# PULSE-CONVERTER.net
KiCad netlist of a schematic drawn in EasyEDA
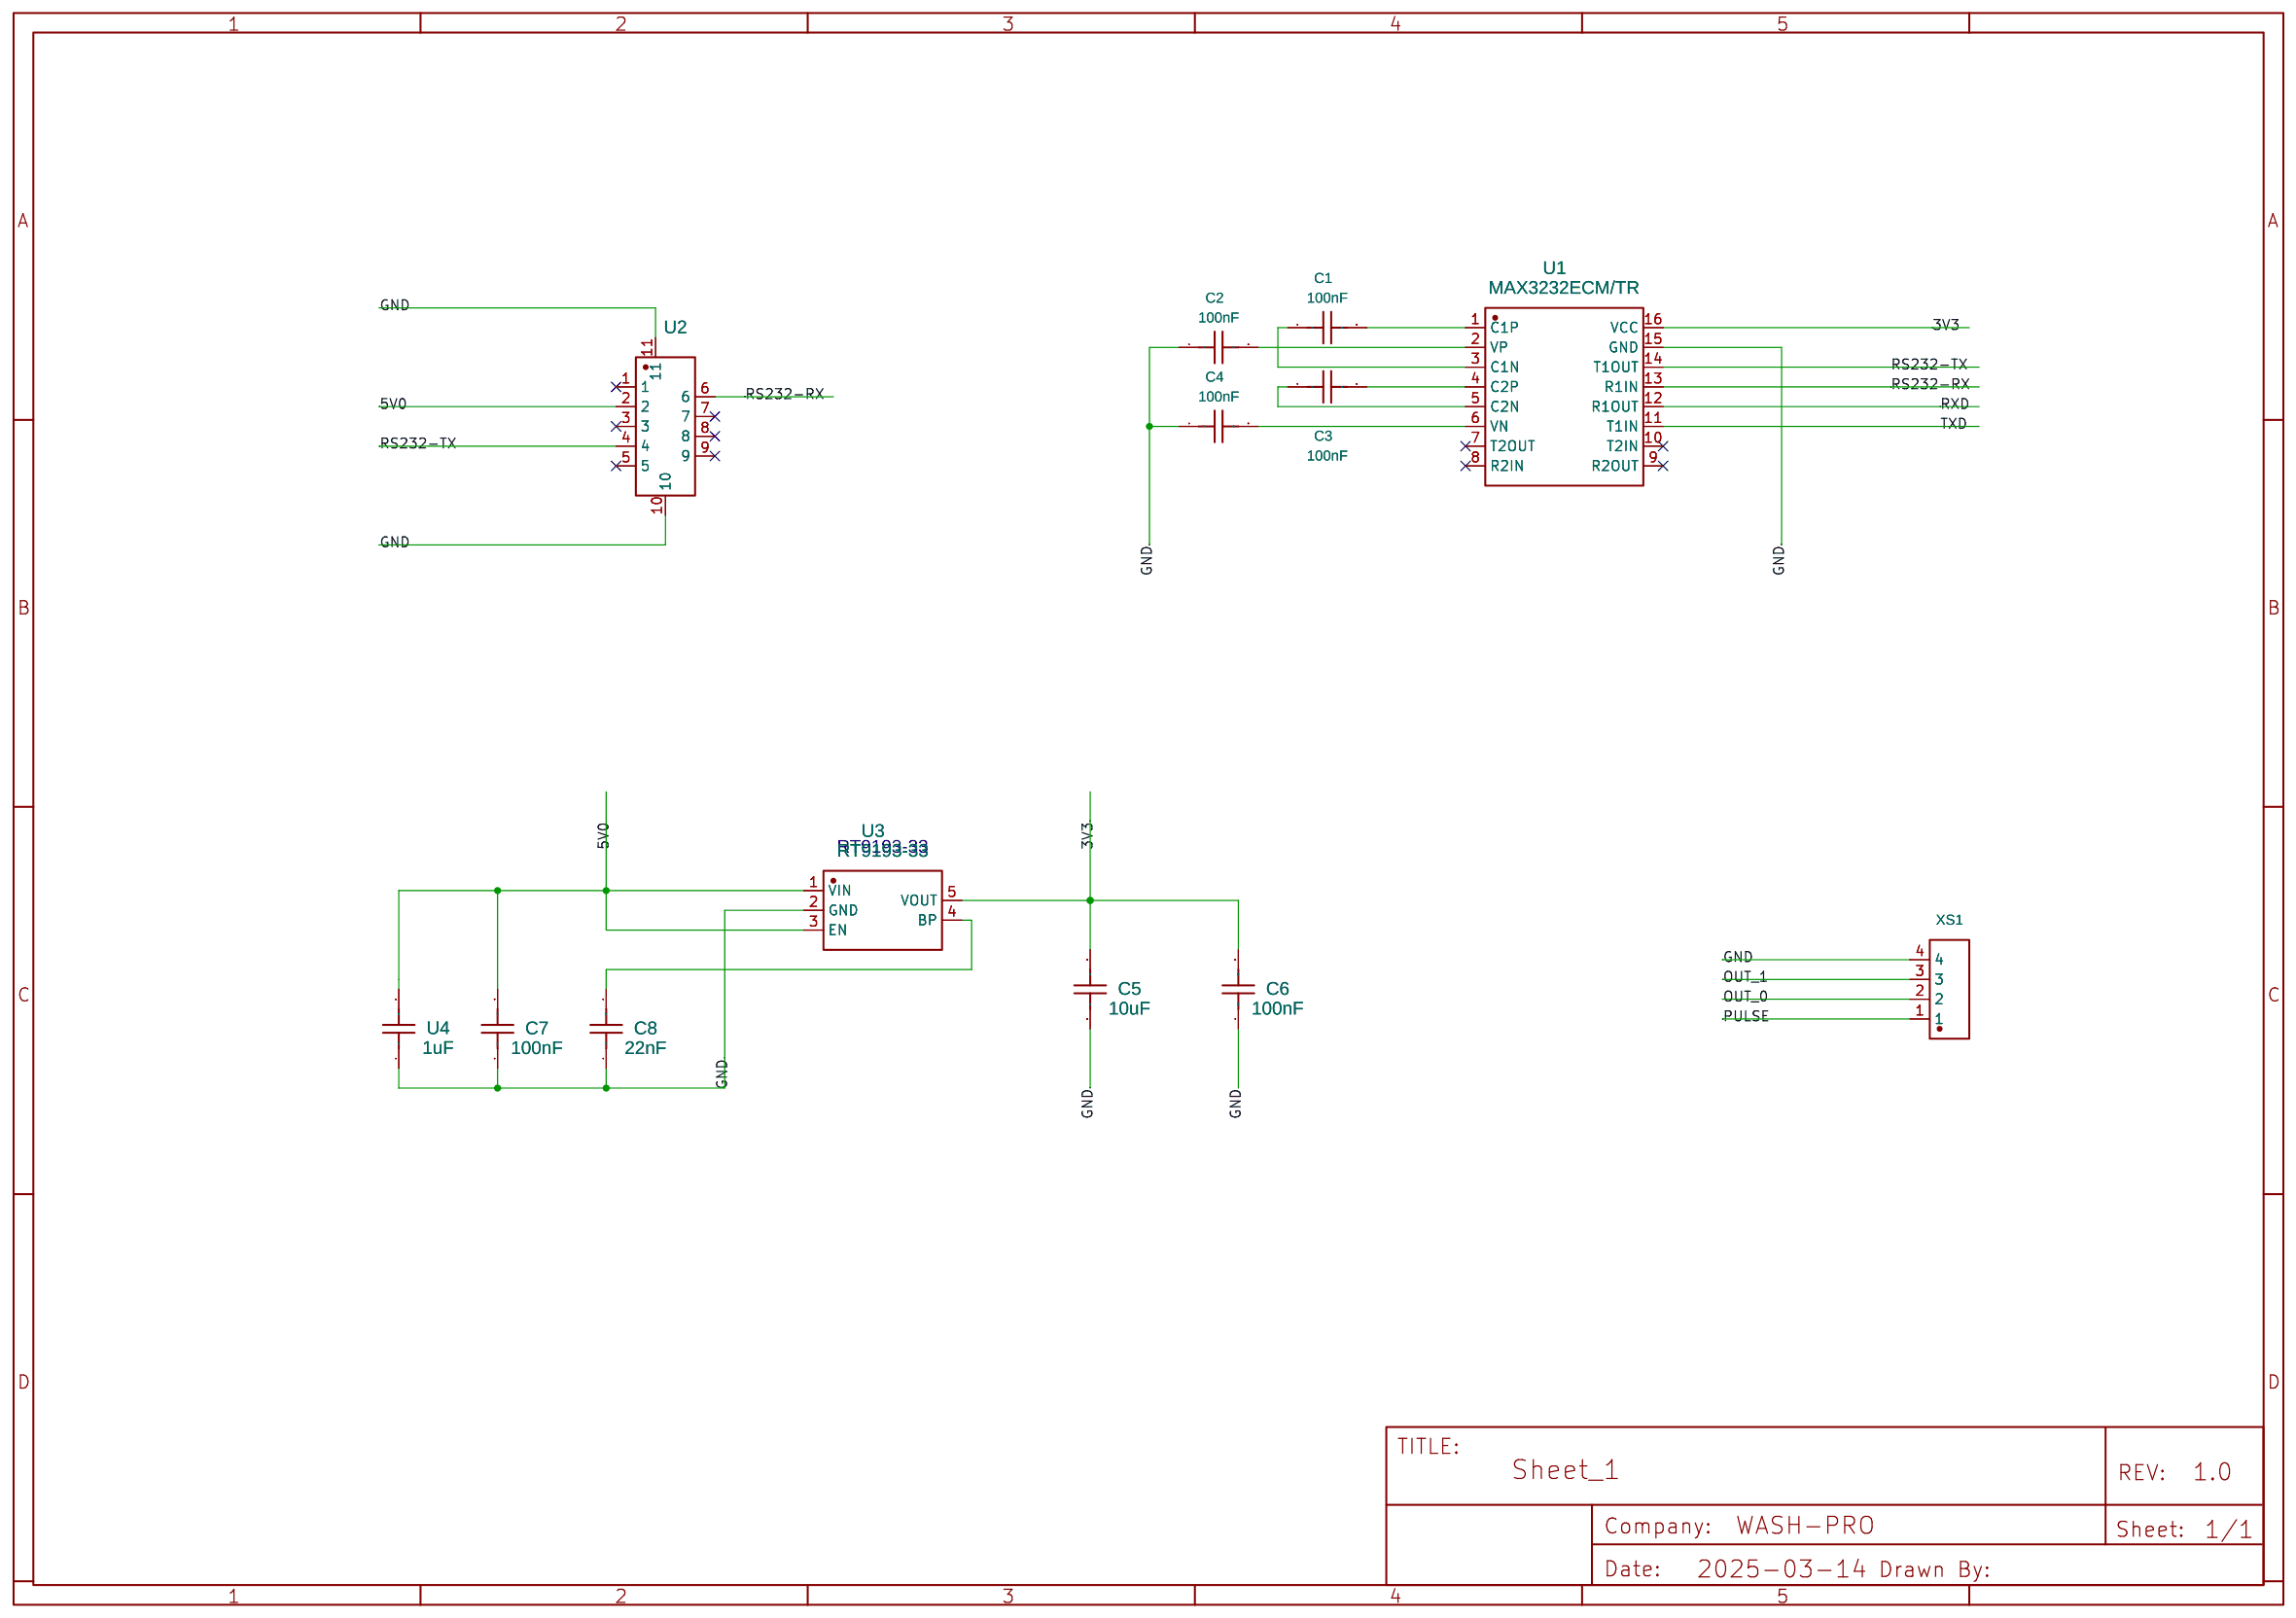
[diagram p0: Sheet_1]
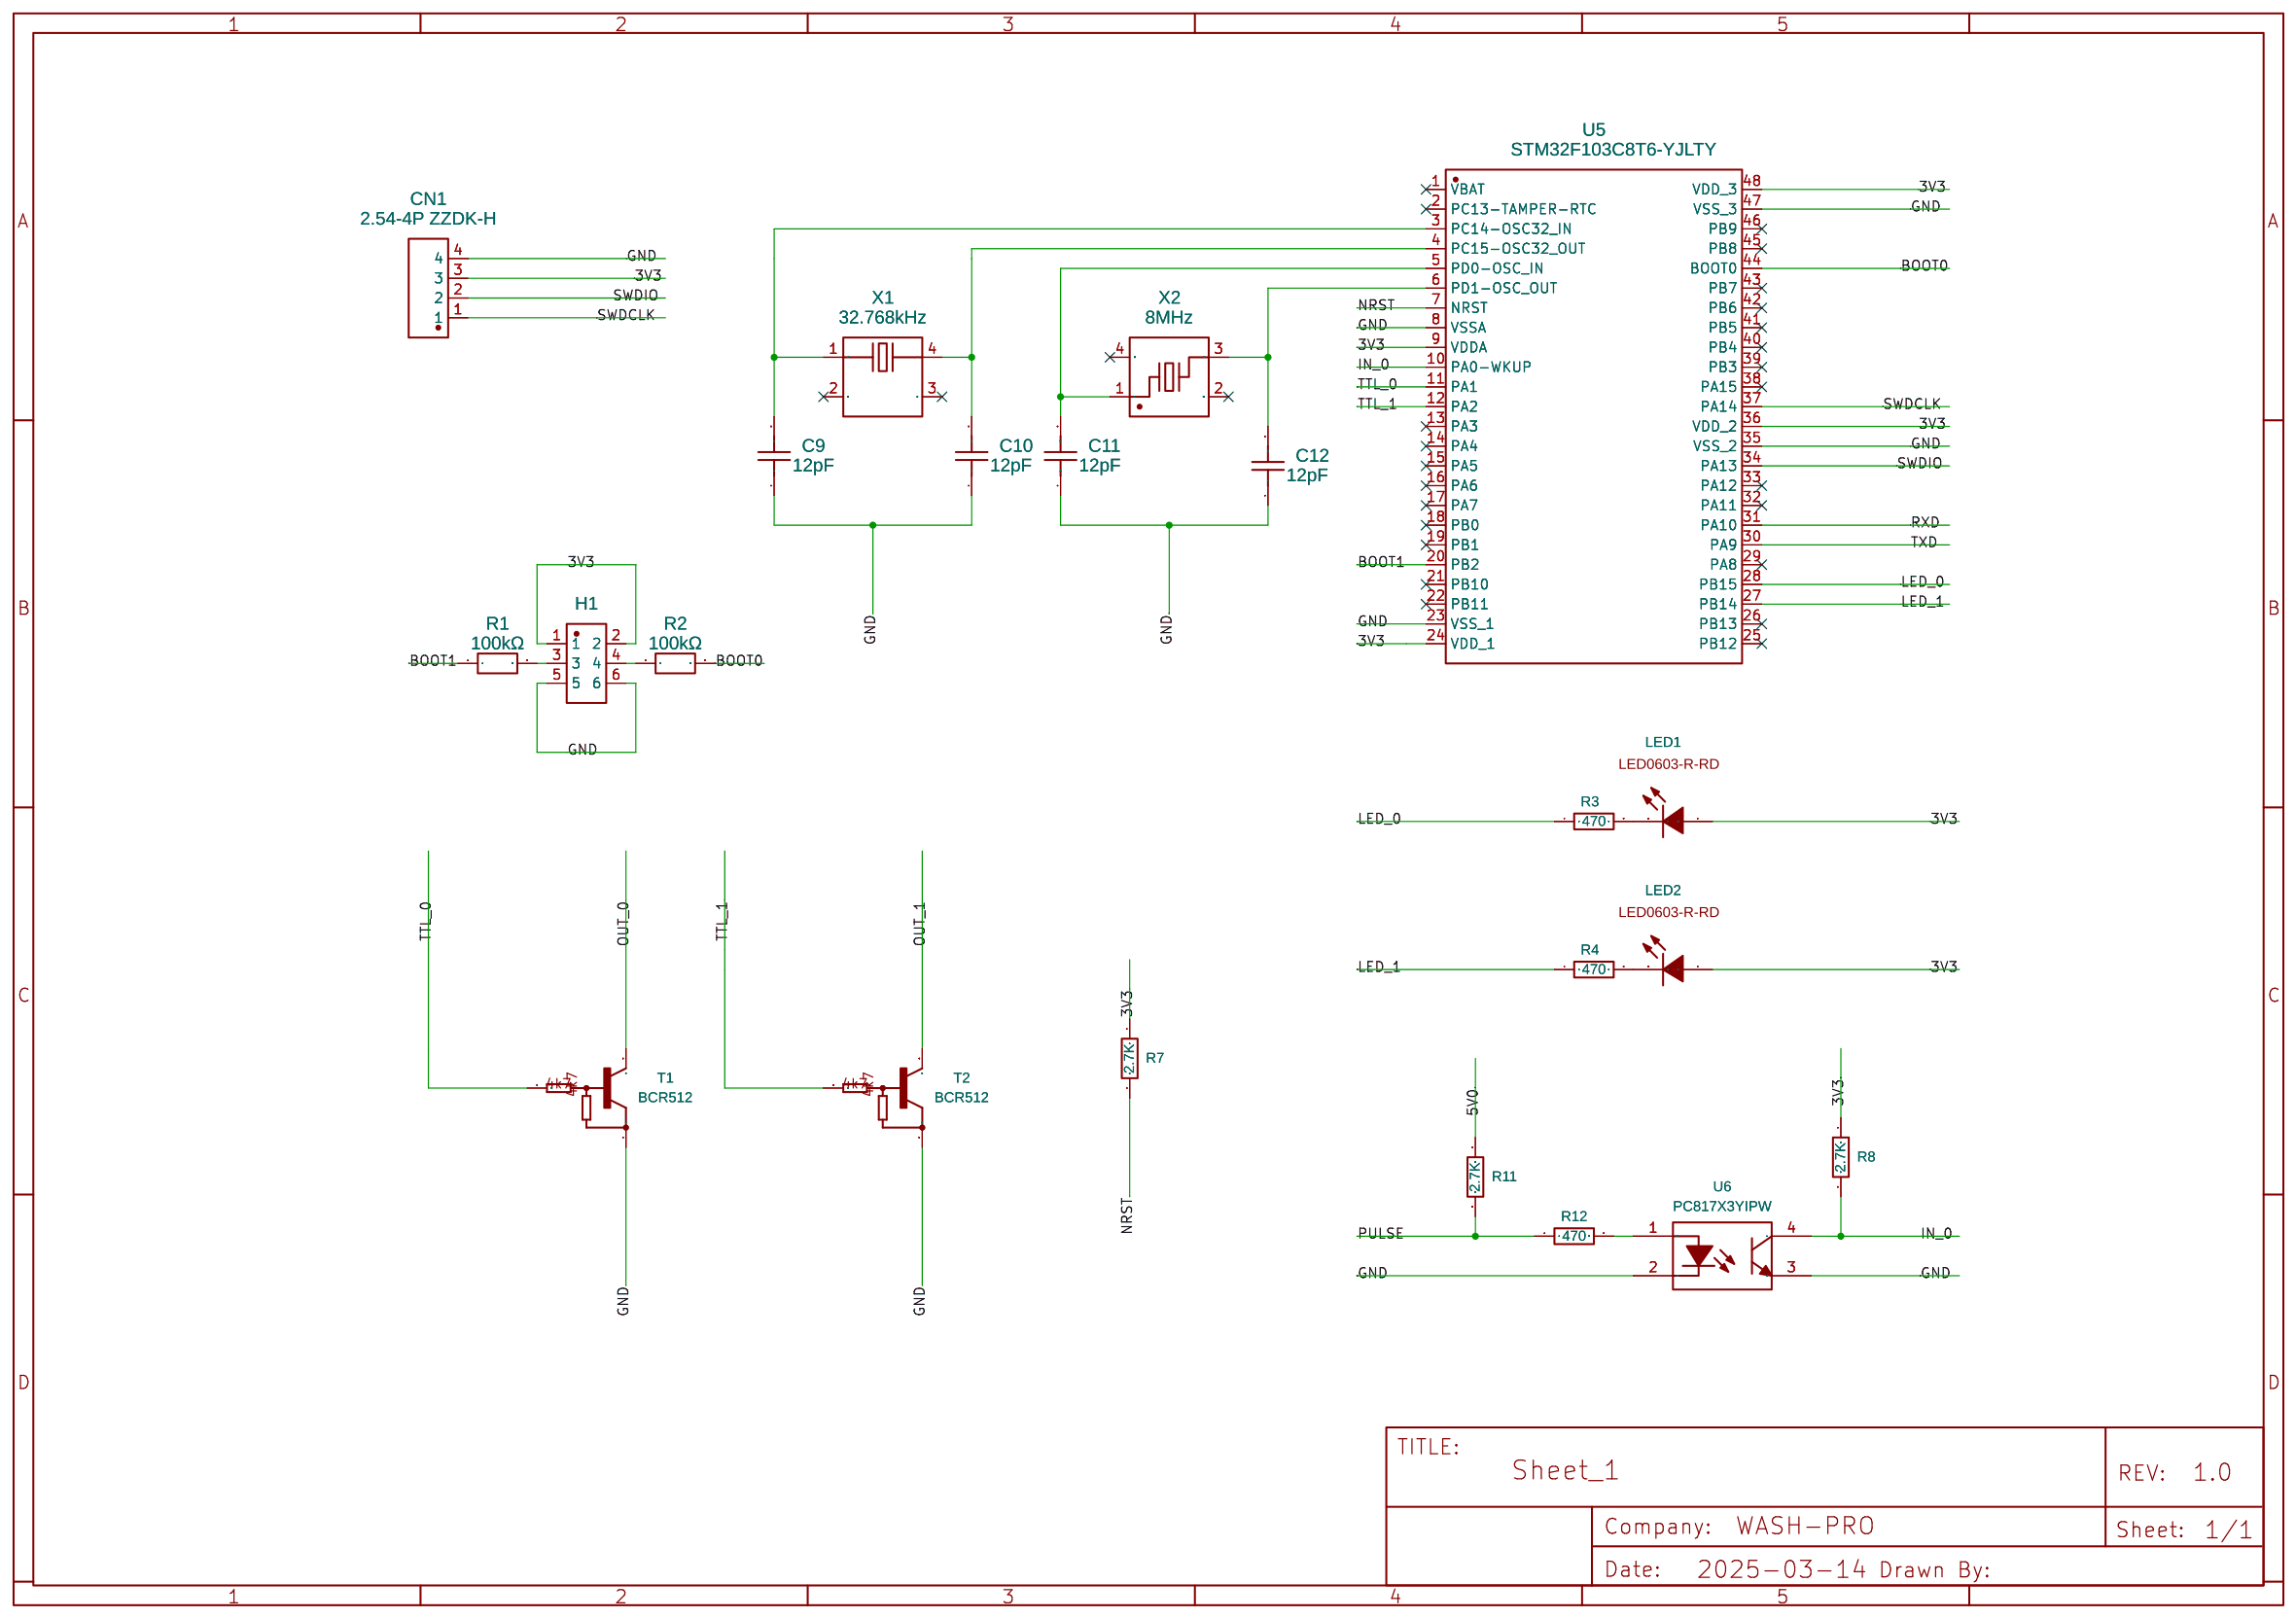
[diagram p1: Sheet_2]

(export (version "E")
  (design (tool "Eeschema 10.0.6"))
  (components
    (comp (ref "C1")
      (value "100nF")
      (fields
        (field (name "Manufacturer Part") "CL21B104KACNFNC")
        (field (name "Manufacturer") "SAMSUNG(三星)")
      )
      (libsource (lib "") (part "CL21B104KACNFNC"))
    )
    (comp (ref "C2")
      (value "100nF")
      (fields
        (field (name "Manufacturer Part") "CL21B104KACNFNC")
        (field (name "Manufacturer") "SAMSUNG(三星)")
      )
      (libsource (lib "") (part "CL21B104KACNFNC"))
    )
    (comp (ref "C3")
      (value "100nF")
      (fields
        (field (name "Manufacturer Part") "CL21B104KACNFNC")
        (field (name "Manufacturer") "SAMSUNG(三星)")
      )
      (libsource (lib "") (part "CL21B104KACNFNC"))
    )
    (comp (ref "C4")
      (value "100nF")
      (fields
        (field (name "Manufacturer Part") "CL21B104KACNFNC")
        (field (name "Manufacturer") "SAMSUNG(三星)")
      )
      (libsource (lib "") (part "CL21B104KACNFNC"))
    )
    (comp (ref "C5")
      (value "10uF")
      (fields (field (name "Manufacturer Part") "CGA4J1X7R0J106M125AD") (field (name "Manufacturer") "TDK"))
      (libsource (lib "") (part "CGA4J1X7R0J106M125AD"))
    )
    (comp (ref "C6")
      (value "100nF")
      (fields (field (name "Manufacturer Part") "C1608X5R1H104K080AA") (field (name "Manufacturer") "TDK"))
      (libsource (lib "") (part "C1608X5R1H104K080AA"))
    )
    (comp (ref "C7")
      (value "100nF")
      (fields (field (name "Manufacturer Part") "C1608X5R1H104K080AA") (field (name "Manufacturer") "TDK"))
      (libsource (lib "") (part "C1608X5R1H104K080AA"))
    )
    (comp (ref "C8")
      (value "22nF")
      (fields (field (name "Manufacturer Part") "C1608X7R2A223K080AE") (field (name "Manufacturer") "TDK"))
      (libsource (lib "") (part "C1608X7R2A223K080AE_C3843204"))
    )
    (comp (ref "U1")
      (value "MAX3232ECM/TR")
      (fields (field (name "Manufacturer") "HGSEMI(华冠)"))
      (libsource (lib "") (part "MAX3232ECM/TR"))
    )
    (comp (ref "U2")
      (value "618009211821")
      (fields (field (name "Manufacturer") "Wurth(伍尔特)"))
      (libsource (lib "") (part "618009211821"))
    )
    (comp (ref "U3") (value "RT9193-33") (libsource (lib "") (part "RT9193-33")))
    (comp (ref "U4")
      (value "1uF")
      (fields (field (name "Manufacturer Part") "C2012X5R1C105M085AA") (field (name "Manufacturer") "TDK"))
      (libsource (lib "") (part "C2012X5R1C105M085AA"))
    )
    (comp (ref "XS1")
      (value "XY2500V-E-3.81-4P")
      (fields (field (name "Manufacturer") "XINLAIYA(新莱亚)"))
      (libsource (lib "") (part "XY2500V-E-3.81-4P"))
    )
    (comp (ref "C9")
      (value "12pF")
      (fields (field (name "Manufacturer Part") "C1608NP01H120J080AA") (field (name "Manufacturer") "TDK"))
      (libsource (lib "") (part "C1608NP01H120J080AA"))
    )
    (comp (ref "C10")
      (value "12pF")
      (fields (field (name "Manufacturer Part") "C1608NP01H120J080AA") (field (name "Manufacturer") "TDK"))
      (libsource (lib "") (part "C1608NP01H120J080AA"))
    )
    (comp (ref "C11")
      (value "12pF")
      (fields (field (name "Manufacturer Part") "C1608NP01H120J080AA") (field (name "Manufacturer") "TDK"))
      (libsource (lib "") (part "C1608NP01H120J080AA"))
    )
    (comp (ref "C12")
      (value "12pF")
      (fields (field (name "Manufacturer Part") "C1608NP01H120J080AA") (field (name "Manufacturer") "TDK"))
      (libsource (lib "") (part "C1608NP01H120J080AA"))
    )
    (comp (ref "CN1")
      (value "2.54-4P ZZDK-H")
      (fields (field (name "Manufacturer") "SHOU HAN(首韩)"))
      (libsource (lib "") (part "2.54-4P ZZDK-H"))
    )
    (comp (ref "H1")
      (value "2.54-2*3")
      (fields (field (name "Manufacturer") "ZHOURI(洲日)"))
      (libsource (lib "") (part "2.54-2*3"))
    )
    (comp (ref "LED1")
      (value "19-217/BHC-XL2M2TY/3T")
      (fields (field (name "Manufacturer") "Everlight Elec"))
      (libsource (lib "") (part "19-217/BHC-XL2M2TY/3T"))
    )
    (comp (ref "LED2")
      (value "19-217/BHC-XL2M2TY/3T")
      (fields (field (name "Manufacturer") "Everlight Elec"))
      (libsource (lib "") (part "19-217/BHC-XL2M2TY/3T"))
    )
    (comp (ref "R1")
      (value "100kΩ")
      (fields (field (name "Manufacturer Part") "RHS-03K1003FT") (field (name "Manufacturer") "FH(风华)"))
      (libsource (lib "") (part "RHS-03K1003FT"))
    )
    (comp (ref "R2")
      (value "100kΩ")
      (fields (field (name "Manufacturer Part") "RHS-03K1003FT") (field (name "Manufacturer") "FH(风华)"))
      (libsource (lib "") (part "RHS-03K1003FT"))
    )
    (comp (ref "R3")
      (value "470")
      (fields (field (name "Manufacturer Part") "RC0603JR-07470RL") (field (name "Manufacturer") "YAGEO"))
      (libsource (lib "") (part "RC0603JR-07470RL"))
    )
    (comp (ref "R4")
      (value "470")
      (fields (field (name "Manufacturer Part") "RC0603JR-07470RL") (field (name "Manufacturer") "YAGEO"))
      (libsource (lib "") (part "RC0603JR-07470RL"))
    )
    (comp (ref "R7")
      (value "2.7K")
      (fields (field (name "Manufacturer Part") "MCR03ERTF1241") (field (name "Manufacturer") "ROHM Semicon"))
      (libsource (lib "") (part "MCR03ERTF1241"))
    )
    (comp (ref "R8")
      (value "2.7K")
      (fields (field (name "Manufacturer Part") "MCR03ERTF1241") (field (name "Manufacturer") "ROHM Semicon"))
      (libsource (lib "") (part "MCR03ERTF1241"))
    )
    (comp (ref "R11")
      (value "2.7K")
      (fields (field (name "Manufacturer Part") "MCR03ERTF1241") (field (name "Manufacturer") "ROHM Semicon"))
      (libsource (lib "") (part "MCR03ERTF1241"))
    )
    (comp (ref "R12")
      (value "470")
      (fields (field (name "Manufacturer Part") "RC0603JR-07470RL") (field (name "Manufacturer") "YAGEO"))
      (libsource (lib "") (part "RC0603JR-07470RL"))
    )
    (comp (ref "T1") (value "BCR512") (libsource (lib "") (part "BCR512")))
    (comp (ref "T2") (value "BCR512") (libsource (lib "") (part "BCR512")))
    (comp (ref "U5") (value "STM32F103C8T6-YJLTY") (libsource (lib "") (part "STM32F103C8T6-YJLTY")))
    (comp (ref "U6")
      (value "PC817X3YIPW")
      (fields (field (name "Manufacturer") "SHARP(夏普)"))
      (libsource (lib "") (part "PC817X3YIPW"))
    )
    (comp (ref "X1")
      (value "32.768kHz")
      (fields
        (field (name "Manufacturer Part") "XKZEL89CII-112YLC-32.768K")
        (field (name "Manufacturer") "YXC(扬兴晶振)")
      )
      (libsource (lib "") (part "XKZEL89CII-112YLC-32.768K"))
    )
    (comp (ref "X2")
      (value "8MHz")
      (fields (field (name "Manufacturer Part") "7U08000E10UCG") (field (name "Manufacturer") "SJK(晶科鑫)"))
      (libsource (lib "") (part "7U08000E10UCG"))
    )
  )
  (nets
    (net (code "1") (name "3V3") (class "Default")
      (node (ref "C5") (pin "2") (pinfunction "2_2") (pintype "unspecified"))
      (node (ref "C6") (pin "2") (pinfunction "2_2") (pintype "unspecified"))
      (node (ref "CN1") (pin "3") (pinfunction "3_3") (pintype "unspecified"))
      (node (ref "H1") (pin "1") (pinfunction "1_1") (pintype "unspecified"))
      (node (ref "H1") (pin "2") (pinfunction "2_2") (pintype "unspecified"))
      (node (ref "LED1") (pin "1") (pinfunction "A_1") (pintype "unspecified"))
      (node (ref "LED2") (pin "1") (pinfunction "A_1") (pintype "unspecified"))
      (node (ref "R7") (pin "1") (pinfunction "1_1") (pintype "unspecified"))
      (node (ref "R8") (pin "1") (pinfunction "1_1") (pintype "unspecified"))
      (node (ref "U1") (pin "16") (pinfunction "VCC_16") (pintype "unspecified"))
      (node (ref "U3") (pin "5") (pinfunction "VOUT_5") (pintype "unspecified"))
      (node (ref "U5") (pin "24") (pinfunction "VDD_1_24") (pintype "unspecified"))
      (node (ref "U5") (pin "36") (pinfunction "VDD_2_36") (pintype "unspecified"))
      (node (ref "U5") (pin "48") (pinfunction "VDD_3_48") (pintype "unspecified"))
      (node (ref "U5") (pin "9") (pinfunction "VDDA_9") (pintype "unspecified"))
    )
    (net (code "2") (name "5V0") (class "Default")
      (node (ref "C7") (pin "2") (pinfunction "2_2") (pintype "unspecified"))
      (node (ref "R11") (pin "1") (pinfunction "1_1") (pintype "unspecified"))
      (node (ref "U2") (pin "2") (pinfunction "2_2") (pintype "unspecified"))
      (node (ref "U3") (pin "1") (pinfunction "VIN_1") (pintype "unspecified"))
      (node (ref "U3") (pin "3") (pinfunction "EN_3") (pintype "unspecified"))
      (node (ref "U4") (pin "2") (pinfunction "2_2") (pintype "unspecified"))
    )
    (net (code "3") (name "BOOT0") (class "Default")
      (node (ref "R2") (pin "2") (pinfunction "2_2") (pintype "unspecified"))
      (node (ref "U5") (pin "44") (pinfunction "BOOT0_44") (pintype "unspecified"))
    )
    (net (code "4") (name "BOOT1") (class "Default")
      (node (ref "R1") (pin "1") (pinfunction "1_1") (pintype "unspecified"))
      (node (ref "U5") (pin "20") (pinfunction "PB2_20") (pintype "unspecified"))
    )
    (net (code "5") (name "GND") (class "Default")
      (node (ref "C10") (pin "1") (pinfunction "1_1") (pintype "unspecified"))
      (node (ref "C11") (pin "1") (pinfunction "1_1") (pintype "unspecified"))
      (node (ref "C12") (pin "1") (pinfunction "1_1") (pintype "unspecified"))
      (node (ref "C2") (pin "1") (pinfunction "1_1") (pintype "unspecified"))
      (node (ref "C4") (pin "1") (pinfunction "1_1") (pintype "unspecified"))
      (node (ref "C5") (pin "1") (pinfunction "1_1") (pintype "unspecified"))
      (node (ref "C6") (pin "1") (pinfunction "1_1") (pintype "unspecified"))
      (node (ref "C7") (pin "1") (pinfunction "1_1") (pintype "unspecified"))
      (node (ref "C8") (pin "1") (pinfunction "1_1") (pintype "unspecified"))
      (node (ref "C9") (pin "1") (pinfunction "1_1") (pintype "unspecified"))
      (node (ref "CN1") (pin "4") (pinfunction "4_4") (pintype "unspecified"))
      (node (ref "H1") (pin "5") (pinfunction "5_5") (pintype "unspecified"))
      (node (ref "H1") (pin "6") (pinfunction "6_6") (pintype "unspecified"))
      (node (ref "T1") (pin "2") (pinfunction "E_2") (pintype "unspecified"))
      (node (ref "T2") (pin "2") (pinfunction "E_2") (pintype "unspecified"))
      (node (ref "U1") (pin "15") (pinfunction "GND_15") (pintype "unspecified"))
      (node (ref "U2") (pin "10") (pinfunction "10_10") (pintype "unspecified"))
      (node (ref "U2") (pin "11") (pinfunction "11_11") (pintype "unspecified"))
      (node (ref "U3") (pin "2") (pinfunction "GND_2") (pintype "unspecified"))
      (node (ref "U4") (pin "1") (pinfunction "1_1") (pintype "unspecified"))
      (node (ref "U5") (pin "23") (pinfunction "VSS_1_23") (pintype "unspecified"))
      (node (ref "U5") (pin "35") (pinfunction "VSS_2_35") (pintype "unspecified"))
      (node (ref "U5") (pin "47") (pinfunction "VSS_3_47") (pintype "unspecified"))
      (node (ref "U5") (pin "8") (pinfunction "VSSA_8") (pintype "unspecified"))
      (node (ref "U6") (pin "2") (pinfunction "2_2") (pintype "unspecified"))
      (node (ref "U6") (pin "3") (pinfunction "3_3") (pintype "unspecified"))
      (node (ref "XS1") (pin "4") (pinfunction "4_4") (pintype "unspecified"))
    )
    (net (code "6") (name "IN_0") (class "Default")
      (node (ref "R8") (pin "2") (pinfunction "2_2") (pintype "unspecified"))
      (node (ref "U5") (pin "10") (pinfunction "PA0-WKUP_10") (pintype "unspecified"))
      (node (ref "U6") (pin "4") (pinfunction "4_4") (pintype "unspecified"))
    )
    (net (code "7") (name "LED_0") (class "Default")
      (node (ref "R3") (pin "1") (pinfunction "1_1") (pintype "input"))
      (node (ref "U5") (pin "28") (pinfunction "PB15_28") (pintype "unspecified"))
    )
    (net (code "8") (name "LED_1") (class "Default")
      (node (ref "R4") (pin "1") (pinfunction "1_1") (pintype "input"))
      (node (ref "U5") (pin "27") (pinfunction "PB14_27") (pintype "unspecified"))
    )
    (net (code "9") (name "NRST") (class "Default")
      (node (ref "R7") (pin "2") (pinfunction "2_2") (pintype "unspecified"))
      (node (ref "U5") (pin "7") (pinfunction "NRST_7") (pintype "unspecified"))
    )
    (net (code "10") (name "Net-(H1-Pad3)") (class "Default")
      (node (ref "H1") (pin "3") (pinfunction "3_3") (pintype "unspecified"))
      (node (ref "R1") (pin "2") (pinfunction "2_2") (pintype "unspecified"))
    )
    (net (code "11") (name "Net-(H1-Pad4)") (class "Default")
      (node (ref "H1") (pin "4") (pinfunction "4_4") (pintype "unspecified"))
      (node (ref "R2") (pin "1") (pinfunction "1_1") (pintype "unspecified"))
    )
    (net (code "12") (name "Net-(LED1-K)") (class "Default")
      (node (ref "LED1") (pin "2") (pinfunction "K_2") (pintype "unspecified"))
      (node (ref "R3") (pin "2") (pinfunction "2_2") (pintype "input"))
    )
    (net (code "13") (name "Net-(LED2-K)") (class "Default")
      (node (ref "LED2") (pin "2") (pinfunction "K_2") (pintype "unspecified"))
      (node (ref "R4") (pin "2") (pinfunction "2_2") (pintype "input"))
    )
    (net (code "14") (name "Net-(R12-Pad2)") (class "Default")
      (node (ref "R12") (pin "2") (pinfunction "2_2") (pintype "input"))
      (node (ref "U6") (pin "1") (pinfunction "1_1") (pintype "unspecified"))
    )
    (net (code "15") (name "Net-(U1-C1N)") (class "Default")
      (node (ref "C1") (pin "1") (pinfunction "1_1") (pintype "unspecified"))
      (node (ref "U1") (pin "3") (pinfunction "C1N_3") (pintype "unspecified"))
    )
    (net (code "16") (name "Net-(U1-C1P)") (class "Default")
      (node (ref "C1") (pin "2") (pinfunction "2_2") (pintype "unspecified"))
      (node (ref "U1") (pin "1") (pinfunction "C1P_1") (pintype "unspecified"))
    )
    (net (code "17") (name "Net-(U1-C2N)") (class "Default")
      (node (ref "C3") (pin "1") (pinfunction "1_1") (pintype "unspecified"))
      (node (ref "U1") (pin "5") (pinfunction "C2N_5") (pintype "unspecified"))
    )
    (net (code "18") (name "Net-(U1-C2P)") (class "Default")
      (node (ref "C3") (pin "2") (pinfunction "2_2") (pintype "unspecified"))
      (node (ref "U1") (pin "4") (pinfunction "C2P_4") (pintype "unspecified"))
    )
    (net (code "19") (name "Net-(U1-VN)") (class "Default")
      (node (ref "C4") (pin "2") (pinfunction "2_2") (pintype "unspecified"))
      (node (ref "U1") (pin "6") (pinfunction "VN_6") (pintype "unspecified"))
    )
    (net (code "20") (name "Net-(U1-VP)") (class "Default")
      (node (ref "C2") (pin "2") (pinfunction "2_2") (pintype "unspecified"))
      (node (ref "U1") (pin "2") (pinfunction "VP_2") (pintype "unspecified"))
    )
    (net (code "21") (name "Net-(U3-BP)") (class "Default")
      (node (ref "C8") (pin "2") (pinfunction "2_2") (pintype "unspecified"))
      (node (ref "U3") (pin "4") (pinfunction "BP_4") (pintype "unspecified"))
    )
    (net (code "22") (name "Net-(U5-PC14-OSC32_IN)") (class "Default")
      (node (ref "C9") (pin "2") (pinfunction "2_2") (pintype "unspecified"))
      (node (ref "U5") (pin "3") (pinfunction "PC14-OSC32_IN_3") (pintype "unspecified"))
      (node (ref "X1") (pin "1") (pinfunction "1_1") (pintype "input"))
    )
    (net (code "23") (name "Net-(U5-PC15-OSC32_OUT)") (class "Default")
      (node (ref "C10") (pin "2") (pinfunction "2_2") (pintype "unspecified"))
      (node (ref "U5") (pin "4") (pinfunction "PC15-OSC32_OUT_4") (pintype "unspecified"))
      (node (ref "X1") (pin "4") (pinfunction "4_4") (pintype "input"))
    )
    (net (code "24") (name "Net-(U5-PD0-OSC_IN)") (class "Default")
      (node (ref "C11") (pin "2") (pinfunction "2_2") (pintype "unspecified"))
      (node (ref "U5") (pin "5") (pinfunction "PD0-OSC_IN_5") (pintype "unspecified"))
      (node (ref "X2") (pin "1") (pinfunction "1_1") (pintype "input"))
    )
    (net (code "25") (name "Net-(U5-PD1-OSC_OUT)") (class "Default")
      (node (ref "C12") (pin "2") (pinfunction "2_2") (pintype "unspecified"))
      (node (ref "U5") (pin "6") (pinfunction "PD1-OSC_OUT_6") (pintype "unspecified"))
      (node (ref "X2") (pin "3") (pinfunction "3_3") (pintype "input"))
    )
    (net (code "26") (name "OUT_0") (class "Default")
      (node (ref "T1") (pin "3") (pinfunction "C_3") (pintype "unspecified"))
      (node (ref "XS1") (pin "2") (pinfunction "2_2") (pintype "unspecified"))
    )
    (net (code "27") (name "OUT_1") (class "Default")
      (node (ref "T2") (pin "3") (pinfunction "C_3") (pintype "unspecified"))
      (node (ref "XS1") (pin "3") (pinfunction "3_3") (pintype "unspecified"))
    )
    (net (code "28") (name "PULSE") (class "Default")
      (node (ref "R11") (pin "2") (pinfunction "2_2") (pintype "unspecified"))
      (node (ref "R12") (pin "1") (pinfunction "1_1") (pintype "input"))
      (node (ref "XS1") (pin "1") (pinfunction "1_1") (pintype "unspecified"))
    )
    (net (code "29") (name "RS232-RX") (class "Default")
      (node (ref "U1") (pin "13") (pinfunction "R1IN_13") (pintype "unspecified"))
      (node (ref "U2") (pin "6") (pinfunction "6_6") (pintype "unspecified"))
    )
    (net (code "30") (name "RS232-TX") (class "Default")
      (node (ref "U1") (pin "14") (pinfunction "T1OUT_14") (pintype "unspecified"))
      (node (ref "U2") (pin "4") (pinfunction "4_4") (pintype "unspecified"))
    )
    (net (code "31") (name "RXD") (class "Default")
      (node (ref "U1") (pin "12") (pinfunction "R1OUT_12") (pintype "unspecified"))
      (node (ref "U5") (pin "31") (pinfunction "PA10_31") (pintype "unspecified"))
    )
    (net (code "32") (name "SWDCLK") (class "Default")
      (node (ref "CN1") (pin "1") (pinfunction "1_1") (pintype "unspecified"))
      (node (ref "U5") (pin "37") (pinfunction "PA14_37") (pintype "unspecified"))
    )
    (net (code "33") (name "SWDIO") (class "Default")
      (node (ref "CN1") (pin "2") (pinfunction "2_2") (pintype "unspecified"))
      (node (ref "U5") (pin "34") (pinfunction "PA13_34") (pintype "unspecified"))
    )
    (net (code "34") (name "TTL_0") (class "Default")
      (node (ref "T1") (pin "1") (pinfunction "B_1") (pintype "unspecified"))
      (node (ref "U5") (pin "11") (pinfunction "PA1_11") (pintype "unspecified"))
    )
    (net (code "35") (name "TTL_1") (class "Default")
      (node (ref "T2") (pin "1") (pinfunction "B_1") (pintype "unspecified"))
      (node (ref "U5") (pin "12") (pinfunction "PA2_12") (pintype "unspecified"))
    )
    (net (code "36") (name "TXD") (class "Default")
      (node (ref "U1") (pin "11") (pinfunction "T1IN_11") (pintype "unspecified"))
      (node (ref "U5") (pin "30") (pinfunction "PA9_30") (pintype "unspecified"))
    )
    (net (code "37") (name "unconnected-(U1-R2IN-Pad8)") (class "Default")
      (node (ref "U1") (pin "8") (pinfunction "R2IN_8") (pintype "unspecified+no_connect"))
    )
    (net (code "38") (name "unconnected-(U1-R2OUT-Pad9)") (class "Default")
      (node (ref "U1") (pin "9") (pinfunction "R2OUT_9") (pintype "unspecified+no_connect"))
    )
    (net (code "39") (name "unconnected-(U1-T2IN-Pad10)") (class "Default")
      (node (ref "U1") (pin "10") (pinfunction "T2IN_10") (pintype "unspecified+no_connect"))
    )
    (net (code "40") (name "unconnected-(U1-T2OUT-Pad7)") (class "Default")
      (node (ref "U1") (pin "7") (pinfunction "T2OUT_7") (pintype "unspecified+no_connect"))
    )
    (net (code "41") (name "unconnected-(U2-Pad1)") (class "Default")
      (node (ref "U2") (pin "1") (pinfunction "1_1") (pintype "unspecified+no_connect"))
    )
    (net (code "42") (name "unconnected-(U2-Pad3)") (class "Default")
      (node (ref "U2") (pin "3") (pinfunction "3_3") (pintype "unspecified+no_connect"))
    )
    (net (code "43") (name "unconnected-(U2-Pad5)") (class "Default")
      (node (ref "U2") (pin "5") (pinfunction "5_5") (pintype "unspecified+no_connect"))
    )
    (net (code "44") (name "unconnected-(U2-Pad7)") (class "Default")
      (node (ref "U2") (pin "7") (pinfunction "7_7") (pintype "unspecified+no_connect"))
    )
    (net (code "45") (name "unconnected-(U2-Pad8)") (class "Default")
      (node (ref "U2") (pin "8") (pinfunction "8_8") (pintype "unspecified+no_connect"))
    )
    (net (code "46") (name "unconnected-(U2-Pad9)") (class "Default")
      (node (ref "U2") (pin "9") (pinfunction "9_9") (pintype "unspecified+no_connect"))
    )
    (net (code "47") (name "unconnected-(U5-PA3-Pad13)") (class "Default")
      (node (ref "U5") (pin "13") (pinfunction "PA3_13") (pintype "unspecified+no_connect"))
    )
    (net (code "48") (name "unconnected-(U5-PA4-Pad14)") (class "Default")
      (node (ref "U5") (pin "14") (pinfunction "PA4_14") (pintype "unspecified+no_connect"))
    )
    (net (code "49") (name "unconnected-(U5-PA5-Pad15)") (class "Default")
      (node (ref "U5") (pin "15") (pinfunction "PA5_15") (pintype "unspecified+no_connect"))
    )
    (net (code "50") (name "unconnected-(U5-PA6-Pad16)") (class "Default")
      (node (ref "U5") (pin "16") (pinfunction "PA6_16") (pintype "unspecified+no_connect"))
    )
    (net (code "51") (name "unconnected-(U5-PA7-Pad17)") (class "Default")
      (node (ref "U5") (pin "17") (pinfunction "PA7_17") (pintype "unspecified+no_connect"))
    )
    (net (code "52") (name "unconnected-(U5-PA8-Pad29)") (class "Default")
      (node (ref "U5") (pin "29") (pinfunction "PA8_29") (pintype "unspecified+no_connect"))
    )
    (net (code "53") (name "unconnected-(U5-PA11-Pad32)") (class "Default")
      (node (ref "U5") (pin "32") (pinfunction "PA11_32") (pintype "unspecified+no_connect"))
    )
    (net (code "54") (name "unconnected-(U5-PA12-Pad33)") (class "Default")
      (node (ref "U5") (pin "33") (pinfunction "PA12_33") (pintype "unspecified+no_connect"))
    )
    (net (code "55") (name "unconnected-(U5-PA15-Pad38)") (class "Default")
      (node (ref "U5") (pin "38") (pinfunction "PA15_38") (pintype "unspecified+no_connect"))
    )
    (net (code "56") (name "unconnected-(U5-PB0-Pad18)") (class "Default")
      (node (ref "U5") (pin "18") (pinfunction "PB0_18") (pintype "unspecified+no_connect"))
    )
    (net (code "57") (name "unconnected-(U5-PB1-Pad19)") (class "Default")
      (node (ref "U5") (pin "19") (pinfunction "PB1_19") (pintype "unspecified+no_connect"))
    )
    (net (code "58") (name "unconnected-(U5-PB3-Pad39)") (class "Default")
      (node (ref "U5") (pin "39") (pinfunction "PB3_39") (pintype "unspecified+no_connect"))
    )
    (net (code "59") (name "unconnected-(U5-PB4-Pad40)") (class "Default")
      (node (ref "U5") (pin "40") (pinfunction "PB4_40") (pintype "unspecified+no_connect"))
    )
    (net (code "60") (name "unconnected-(U5-PB5-Pad41)") (class "Default")
      (node (ref "U5") (pin "41") (pinfunction "PB5_41") (pintype "unspecified+no_connect"))
    )
    (net (code "61") (name "unconnected-(U5-PB6-Pad42)") (class "Default")
      (node (ref "U5") (pin "42") (pinfunction "PB6_42") (pintype "unspecified+no_connect"))
    )
    (net (code "62") (name "unconnected-(U5-PB7-Pad43)") (class "Default")
      (node (ref "U5") (pin "43") (pinfunction "PB7_43") (pintype "unspecified+no_connect"))
    )
    (net (code "63") (name "unconnected-(U5-PB8-Pad45)") (class "Default")
      (node (ref "U5") (pin "45") (pinfunction "PB8_45") (pintype "unspecified+no_connect"))
    )
    (net (code "64") (name "unconnected-(U5-PB9-Pad46)") (class "Default")
      (node (ref "U5") (pin "46") (pinfunction "PB9_46") (pintype "unspecified+no_connect"))
    )
    (net (code "65") (name "unconnected-(U5-PB10-Pad21)") (class "Default")
      (node (ref "U5") (pin "21") (pinfunction "PB10_21") (pintype "unspecified+no_connect"))
    )
    (net (code "66") (name "unconnected-(U5-PB11-Pad22)") (class "Default")
      (node (ref "U5") (pin "22") (pinfunction "PB11_22") (pintype "unspecified+no_connect"))
    )
    (net (code "67") (name "unconnected-(U5-PB12-Pad25)") (class "Default")
      (node (ref "U5") (pin "25") (pinfunction "PB12_25") (pintype "unspecified+no_connect"))
    )
    (net (code "68") (name "unconnected-(U5-PB13-Pad26)") (class "Default")
      (node (ref "U5") (pin "26") (pinfunction "PB13_26") (pintype "unspecified+no_connect"))
    )
    (net (code "69") (name "unconnected-(U5-PC13-TAMPER-RTC-Pad2)") (class "Default")
      (node (ref "U5") (pin "2") (pinfunction "PC13-TAMPER-RTC_2") (pintype "unspecified+no_connect"))
    )
    (net (code "70") (name "unconnected-(U5-VBAT-Pad1)") (class "Default")
      (node (ref "U5") (pin "1") (pinfunction "VBAT_1") (pintype "unspecified+no_connect"))
    )
    (net (code "71") (name "unconnected-(X1-Pad2)") (class "Default")
      (node (ref "X1") (pin "2") (pinfunction "2_2") (pintype "input+no_connect"))
    )
    (net (code "72") (name "unconnected-(X1-Pad3)") (class "Default")
      (node (ref "X1") (pin "3") (pinfunction "3_3") (pintype "input+no_connect"))
    )
    (net (code "73") (name "unconnected-(X2-GND-Pad2)") (class "Default")
      (node (ref "X2") (pin "2") (pinfunction "GND_2") (pintype "input+no_connect"))
    )
    (net (code "74") (name "unconnected-(X2-GND-Pad4)") (class "Default")
      (node (ref "X2") (pin "4") (pinfunction "GND_4") (pintype "input+no_connect"))
    )
  )
)
